# esquematico.net
KiCad netlist of a schematic drawn in Altium Designer
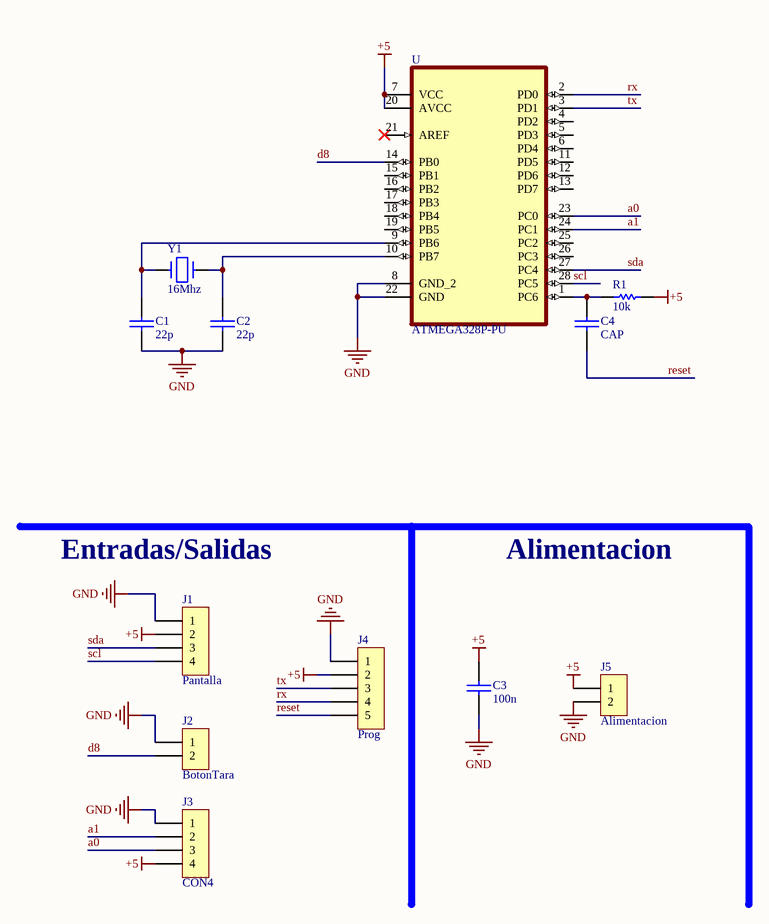
[diagram p0: esquematico.SchDoc]

(export (version "E")
  (design (tool "Eeschema 10.0.6"))
  (components
    (comp (ref "C1") (value "22p") (footprint "CAP200") (libsource (lib "LIBEBAL") (part "CAP")))
    (comp (ref "C2") (value "22p") (footprint "CAP200") (libsource (lib "LIBEBAL") (part "CAP")))
    (comp (ref "C3") (value "100n") (footprint "CAP200") (libsource (lib "LIBEBAL") (part "CAP")))
    (comp (ref "C4") (value "CAP") (footprint "CAP200") (libsource (lib "LIBEBAL") (part "CAP")))
    (comp (ref "J1") (value "Pantalla") (footprint "SIP4") (libsource (lib "LIBEBAL") (part "CON4")))
    (comp (ref "J2") (value "BotonTara") (footprint "SIP2") (libsource (lib "LIBEBAL") (part "CON2")))
    (comp (ref "J3") (value "CON4") (footprint "SIP4") (libsource (lib "LIBEBAL") (part "CON4")))
    (comp (ref "J4") (value "Prog") (footprint "SIP5") (libsource (lib "LIBEBAL") (part "CON5")))
    (comp (ref "J5")
      (value "Alimentacion")
      (footprint "BORNERA2")
      (libsource (lib "LIBEBAL") (part "BORNERA 2"))
    )
    (comp (ref "R1") (value "10k") (footprint "RES400") (libsource (lib "LIBEBAL") (part "RES")))
    (comp (ref "U")
      (value "ATMEGA328P-PU")
      (footprint "DIP254P762X457-28")
      (description "AVR AVRÂ® ATmega Microcontroller IC 8-Bit 20MHz 32KB _16K x 16_ FLASH 28-PDIP")
      (fields (field (name "MF") "Microchip"))
      (libsource (lib "ATMEGA328P-PU") (part "ATMEGA328P-PU"))
    )
    (comp (ref "Y1")
      (value "16Mhz")
      (footprint "CRISTAL PERFIL")
      (libsource (lib "LIBEBAL") (part "CRISTAL"))
    )
  )
  (nets
    (net (code "1") (name "+5") (class "Default")
      (node (ref "C3") (pin "1") (pinfunction "1_1") (pintype "passive"))
      (node (ref "J1") (pin "2") (pinfunction "2_2") (pintype "passive"))
      (node (ref "J3") (pin "4") (pinfunction "4_4") (pintype "passive"))
      (node (ref "J4") (pin "2") (pinfunction "2_2") (pintype "passive"))
      (node (ref "J5") (pin "1") (pinfunction "1_1") (pintype "passive"))
      (node (ref "R1") (pin "2") (pinfunction "2_2") (pintype "passive"))
      (node (ref "U") (pin "20") (pinfunction "AVCC_20") (pintype "power_in"))
      (node (ref "U") (pin "7") (pinfunction "VCC_7") (pintype "power_in"))
    )
    (net (code "2") (name "/a0") (class "Default")
      (node (ref "J3") (pin "3") (pinfunction "3_3") (pintype "passive"))
      (node (ref "U") (pin "23") (pinfunction "PC0_23") (pintype "bidirectional"))
    )
    (net (code "3") (name "/a1") (class "Default")
      (node (ref "J3") (pin "2") (pinfunction "2_2") (pintype "passive"))
      (node (ref "U") (pin "24") (pinfunction "PC1_24") (pintype "bidirectional"))
    )
    (net (code "4") (name "/d8") (class "Default")
      (node (ref "J2") (pin "2") (pinfunction "2_2") (pintype "passive"))
      (node (ref "U") (pin "14") (pinfunction "PB0_14") (pintype "bidirectional"))
    )
    (net (code "5") (name "/reset") (class "Default")
      (node (ref "C4") (pin "2") (pinfunction "2_2") (pintype "passive"))
      (node (ref "J4") (pin "5") (pinfunction "5_5") (pintype "passive"))
    )
    (net (code "6") (name "/rx") (class "Default")
      (node (ref "J4") (pin "4") (pinfunction "4_4") (pintype "passive"))
      (node (ref "U") (pin "2") (pinfunction "PD0_2") (pintype "bidirectional"))
    )
    (net (code "7") (name "/scl") (class "Default")
      (node (ref "J1") (pin "4") (pinfunction "4_4") (pintype "passive"))
      (node (ref "U") (pin "28") (pinfunction "PC5_28") (pintype "bidirectional"))
    )
    (net (code "8") (name "/sda") (class "Default")
      (node (ref "J1") (pin "3") (pinfunction "3_3") (pintype "passive"))
      (node (ref "U") (pin "27") (pinfunction "PC4_27") (pintype "bidirectional"))
    )
    (net (code "9") (name "/tx") (class "Default")
      (node (ref "J4") (pin "3") (pinfunction "3_3") (pintype "passive"))
      (node (ref "U") (pin "3") (pinfunction "PD1_3") (pintype "bidirectional"))
    )
    (net (code "10") (name "GND") (class "Default")
      (node (ref "C1") (pin "2") (pinfunction "2_2") (pintype "passive"))
      (node (ref "C2") (pin "2") (pinfunction "2_2") (pintype "passive"))
      (node (ref "C3") (pin "2") (pinfunction "2_2") (pintype "passive"))
      (node (ref "J1") (pin "1") (pinfunction "1_1") (pintype "passive"))
      (node (ref "J2") (pin "1") (pinfunction "1_1") (pintype "passive"))
      (node (ref "J3") (pin "1") (pinfunction "1_1") (pintype "passive"))
      (node (ref "J4") (pin "1") (pinfunction "1_1") (pintype "passive"))
      (node (ref "J5") (pin "2") (pinfunction "2_2") (pintype "passive"))
      (node (ref "U") (pin "22") (pinfunction "GND_22") (pintype "passive"))
      (node (ref "U") (pin "8") (pinfunction "GND_2_8") (pintype "passive"))
    )
    (net (code "11") (name "Net-(U-PB6)") (class "Default")
      (node (ref "C1") (pin "1") (pinfunction "1_1") (pintype "passive"))
      (node (ref "U") (pin "9") (pinfunction "PB6_9") (pintype "bidirectional"))
      (node (ref "Y1") (pin "1") (pinfunction "1_1") (pintype "passive"))
    )
    (net (code "12") (name "Net-(U-PB7)") (class "Default")
      (node (ref "C2") (pin "1") (pinfunction "1_1") (pintype "passive"))
      (node (ref "U") (pin "10") (pinfunction "PB7_10") (pintype "bidirectional"))
      (node (ref "Y1") (pin "2") (pinfunction "10_2") (pintype "passive"))
    )
    (net (code "13") (name "Net-(U-PC6)") (class "Default")
      (node (ref "C4") (pin "1") (pinfunction "1_1") (pintype "passive"))
      (node (ref "R1") (pin "1") (pinfunction "1_1") (pintype "passive"))
      (node (ref "U") (pin "1") (pinfunction "PC6_1") (pintype "bidirectional"))
    )
    (net (code "14") (name "unconnected-(U-AREF-Pad21)") (class "Default")
      (node (ref "U") (pin "21") (pinfunction "AREF_21") (pintype "input+no_connect"))
    )
    (net (code "15") (name "unconnected-(U-PB1-Pad15)") (class "Default")
      (node (ref "U") (pin "15") (pinfunction "PB1_15") (pintype "bidirectional"))
    )
    (net (code "16") (name "unconnected-(U-PB2-Pad16)") (class "Default")
      (node (ref "U") (pin "16") (pinfunction "PB2_16") (pintype "bidirectional"))
    )
    (net (code "17") (name "unconnected-(U-PB3-Pad17)") (class "Default")
      (node (ref "U") (pin "17") (pinfunction "PB3_17") (pintype "bidirectional"))
    )
    (net (code "18") (name "unconnected-(U-PB4-Pad18)") (class "Default")
      (node (ref "U") (pin "18") (pinfunction "PB4_18") (pintype "bidirectional"))
    )
    (net (code "19") (name "unconnected-(U-PB5-Pad19)") (class "Default")
      (node (ref "U") (pin "19") (pinfunction "PB5_19") (pintype "bidirectional"))
    )
    (net (code "20") (name "unconnected-(U-PC2-Pad25)") (class "Default")
      (node (ref "U") (pin "25") (pinfunction "PC2_25") (pintype "bidirectional"))
    )
    (net (code "21") (name "unconnected-(U-PC3-Pad26)") (class "Default")
      (node (ref "U") (pin "26") (pinfunction "PC3_26") (pintype "bidirectional"))
    )
    (net (code "22") (name "unconnected-(U-PD2-Pad4)") (class "Default")
      (node (ref "U") (pin "4") (pinfunction "PD2_4") (pintype "bidirectional"))
    )
    (net (code "23") (name "unconnected-(U-PD3-Pad5)") (class "Default")
      (node (ref "U") (pin "5") (pinfunction "PD3_5") (pintype "bidirectional"))
    )
    (net (code "24") (name "unconnected-(U-PD4-Pad6)") (class "Default")
      (node (ref "U") (pin "6") (pinfunction "PD4_6") (pintype "bidirectional"))
    )
    (net (code "25") (name "unconnected-(U-PD5-Pad11)") (class "Default")
      (node (ref "U") (pin "11") (pinfunction "PD5_11") (pintype "bidirectional"))
    )
    (net (code "26") (name "unconnected-(U-PD6-Pad12)") (class "Default")
      (node (ref "U") (pin "12") (pinfunction "PD6_12") (pintype "bidirectional"))
    )
    (net (code "27") (name "unconnected-(U-PD7-Pad13)") (class "Default")
      (node (ref "U") (pin "13") (pinfunction "PD7_13") (pintype "bidirectional"))
    )
  )
)
